# attiny85breakout.net
KiCad netlist of a schematic drawn in EAGLE
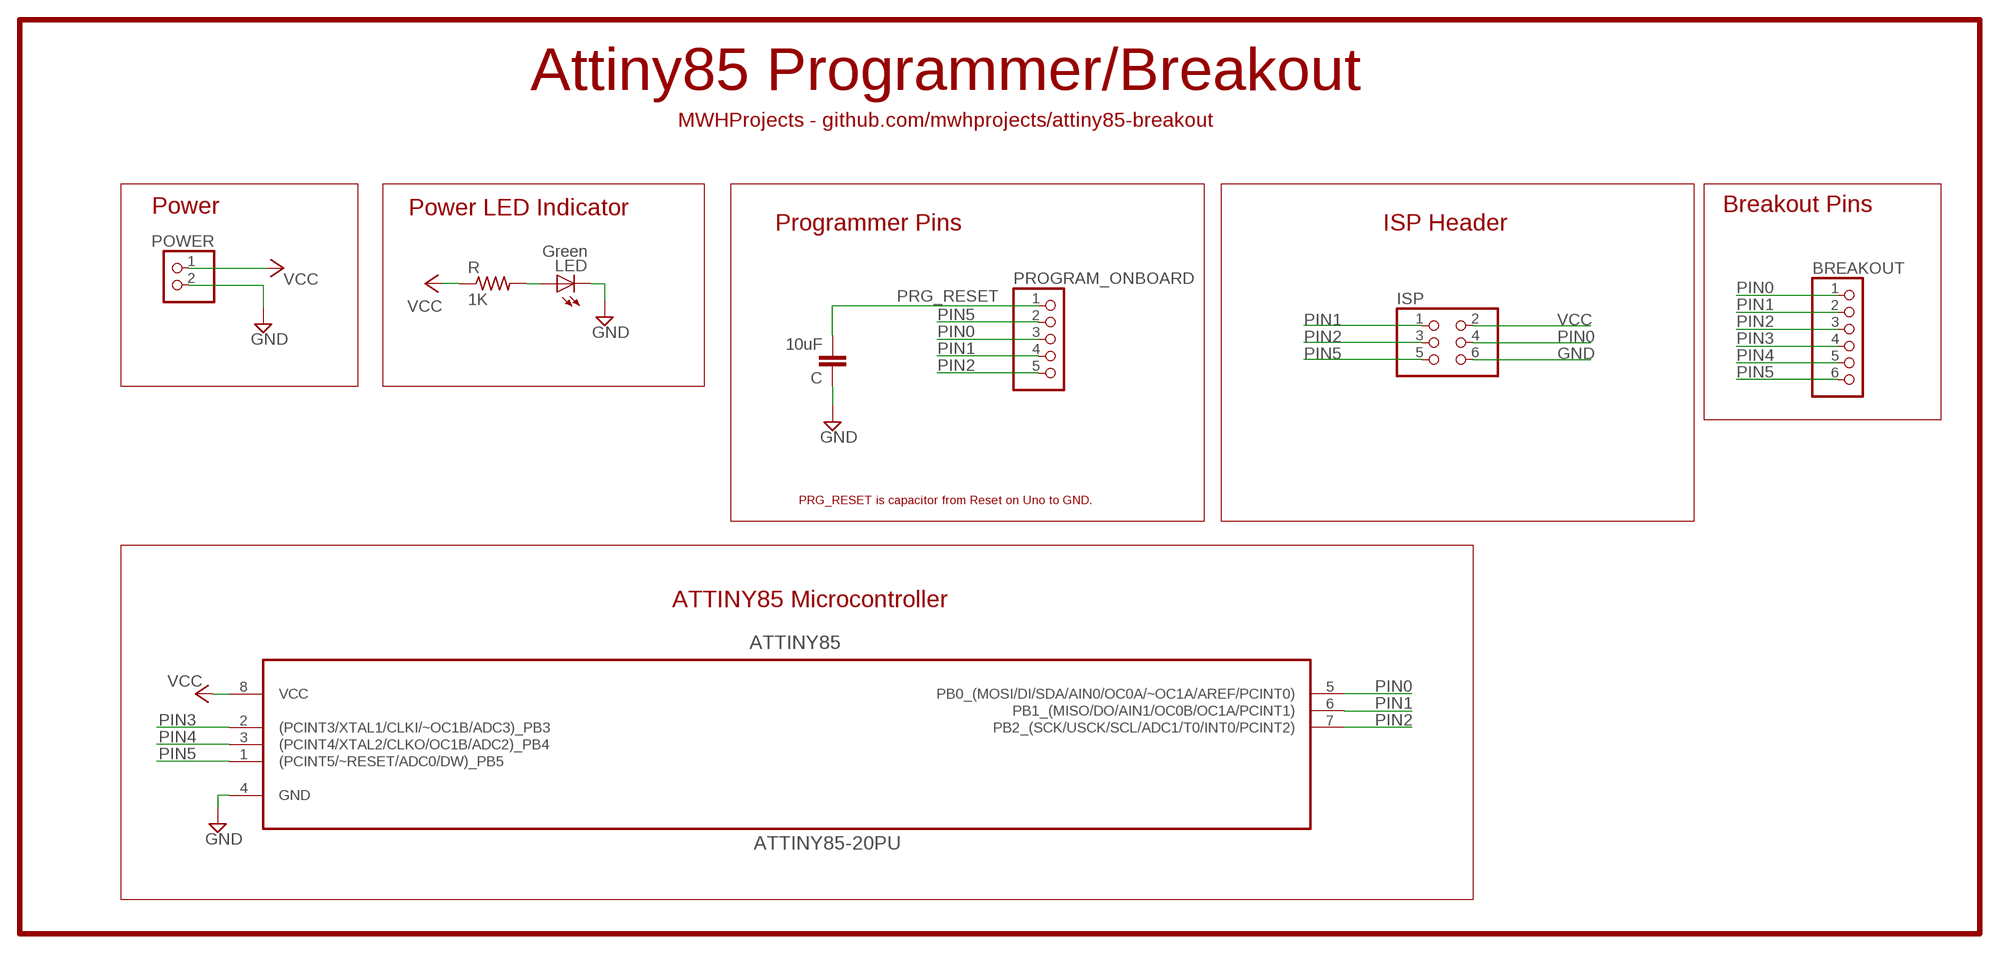
[diagram p0: schematic, sheet 1]

(export (version "E")
  (design (tool "Eeschema 10.0.6"))
  (components
    (comp (ref "ATTINY85")
      (value "ATTINY85-20PU")
      (footprint "eagle-import:DIP254P762X533-8")
      (libsource (lib "eagle-import") (part "ATTINY85-20PU"))
    )
    (comp (ref "BREAKOUT")
      (value "0")
      (footprint "eagle-import:1X06")
      (libsource (lib "eagle-import") (part "PINHD-1X6"))
    )
    (comp (ref "C")
      (value "10uF")
      (footprint "eagle-import:C0805")
      (libsource (lib "eagle-import") (part "C-EUC0805"))
    )
    (comp (ref "ISP")
      (value "PINHD-2X3")
      (footprint "eagle-import:2X03")
      (libsource (lib "eagle-import") (part "PINHD-2X3"))
    )
    (comp (ref "LED")
      (value "Green")
      (footprint "eagle-import:CHIP-LED0805")
      (libsource (lib "eagle-import") (part "LEDCHIP-LED0805"))
    )
    (comp (ref "POWER")
      (value "0")
      (footprint "eagle-import:1X02")
      (libsource (lib "eagle-import") (part "PINHD-1X2"))
    )
    (comp (ref "PROGRAM_ONBOARD")
      (value "0")
      (footprint "eagle-import:1X05")
      (libsource (lib "eagle-import") (part "PINHD-1X5"))
    )
    (comp (ref "R")
      (value "1K")
      (footprint "eagle-import:R0805")
      (libsource (lib "eagle-import") (part "R-US_R0805"))
    )
  )
  (nets
    (net (code "1") (name "/PIN0") (class "Default")
      (node (ref "ATTINY85") (pin "5") (pinfunction "PB0_(MOSI/DI/SDA/AIN0/OC0A/~{OC1A/AREF/PCINT0})_5") (pintype "bidirectional"))
      (node (ref "BREAKOUT") (pin "1") (pinfunction "1_1") (pintype "passive"))
      (node (ref "ISP") (pin "4") (pinfunction "4_4") (pintype "passive"))
      (node (ref "PROGRAM_ONBOARD") (pin "3") (pinfunction "3_3") (pintype "passive"))
    )
    (net (code "2") (name "/PIN1") (class "Default")
      (node (ref "ATTINY85") (pin "6") (pinfunction "PB1_(MISO/DO/AIN1/OC0B/OC1A/PCINT1)_6") (pintype "bidirectional"))
      (node (ref "BREAKOUT") (pin "2") (pinfunction "2_2") (pintype "passive"))
      (node (ref "ISP") (pin "1") (pinfunction "1_1") (pintype "passive"))
      (node (ref "PROGRAM_ONBOARD") (pin "4") (pinfunction "4_4") (pintype "passive"))
    )
    (net (code "3") (name "/PIN2") (class "Default")
      (node (ref "ATTINY85") (pin "7") (pinfunction "PB2_(SCK/USCK/SCL/ADC1/T0/INT0/PCINT2)_7") (pintype "bidirectional"))
      (node (ref "BREAKOUT") (pin "3") (pinfunction "3_3") (pintype "passive"))
      (node (ref "ISP") (pin "3") (pinfunction "3_3") (pintype "passive"))
      (node (ref "PROGRAM_ONBOARD") (pin "5") (pinfunction "5_5") (pintype "passive"))
    )
    (net (code "4") (name "/PIN3") (class "Default")
      (node (ref "ATTINY85") (pin "2") (pinfunction "(PCINT3/XTAL1/CLKI/~{OC1B/ADC3})_PB3_2") (pintype "bidirectional"))
      (node (ref "BREAKOUT") (pin "4") (pinfunction "4_4") (pintype "passive"))
    )
    (net (code "5") (name "/PIN4") (class "Default")
      (node (ref "ATTINY85") (pin "3") (pinfunction "(PCINT4/XTAL2/CLKO/OC1B/ADC2)_PB4_3") (pintype "bidirectional"))
      (node (ref "BREAKOUT") (pin "5") (pinfunction "5_5") (pintype "passive"))
    )
    (net (code "6") (name "/PIN5") (class "Default")
      (node (ref "ATTINY85") (pin "1") (pinfunction "(PCINT5/~{RESET/ADC0/DW})_PB5_1") (pintype "bidirectional"))
      (node (ref "BREAKOUT") (pin "6") (pinfunction "6_6") (pintype "passive"))
      (node (ref "ISP") (pin "5") (pinfunction "5_5") (pintype "passive"))
      (node (ref "PROGRAM_ONBOARD") (pin "2") (pinfunction "2_2") (pintype "passive"))
    )
    (net (code "7") (name "/PRG_RESET") (class "Default")
      (node (ref "C") (pin "2") (pinfunction "2_2") (pintype "passive"))
      (node (ref "PROGRAM_ONBOARD") (pin "1") (pinfunction "1_1") (pintype "passive"))
    )
    (net (code "8") (name "GND") (class "Default")
      (node (ref "ATTINY85") (pin "4") (pinfunction "GND_4") (pintype "passive"))
      (node (ref "C") (pin "1") (pinfunction "1_1") (pintype "passive"))
      (node (ref "ISP") (pin "6") (pinfunction "6_6") (pintype "passive"))
      (node (ref "LED") (pin "C") (pinfunction "C_C") (pintype "passive"))
      (node (ref "POWER") (pin "2") (pinfunction "2_2") (pintype "passive"))
    )
    (net (code "9") (name "Net-(LED-PadA)") (class "Default")
      (node (ref "LED") (pin "A") (pinfunction "A_A") (pintype "passive"))
      (node (ref "R") (pin "2") (pinfunction "2_2") (pintype "passive"))
    )
    (net (code "10") (name "VCC") (class "Default")
      (node (ref "ATTINY85") (pin "8") (pinfunction "VCC_8") (pintype "power_in"))
      (node (ref "ISP") (pin "2") (pinfunction "2_2") (pintype "passive"))
      (node (ref "POWER") (pin "1") (pinfunction "1_1") (pintype "passive"))
      (node (ref "R") (pin "1") (pinfunction "1_1") (pintype "passive"))
    )
  )
)
